# power_distribution_pcb.net
KiCad netlist of a schematic drawn in EAGLE
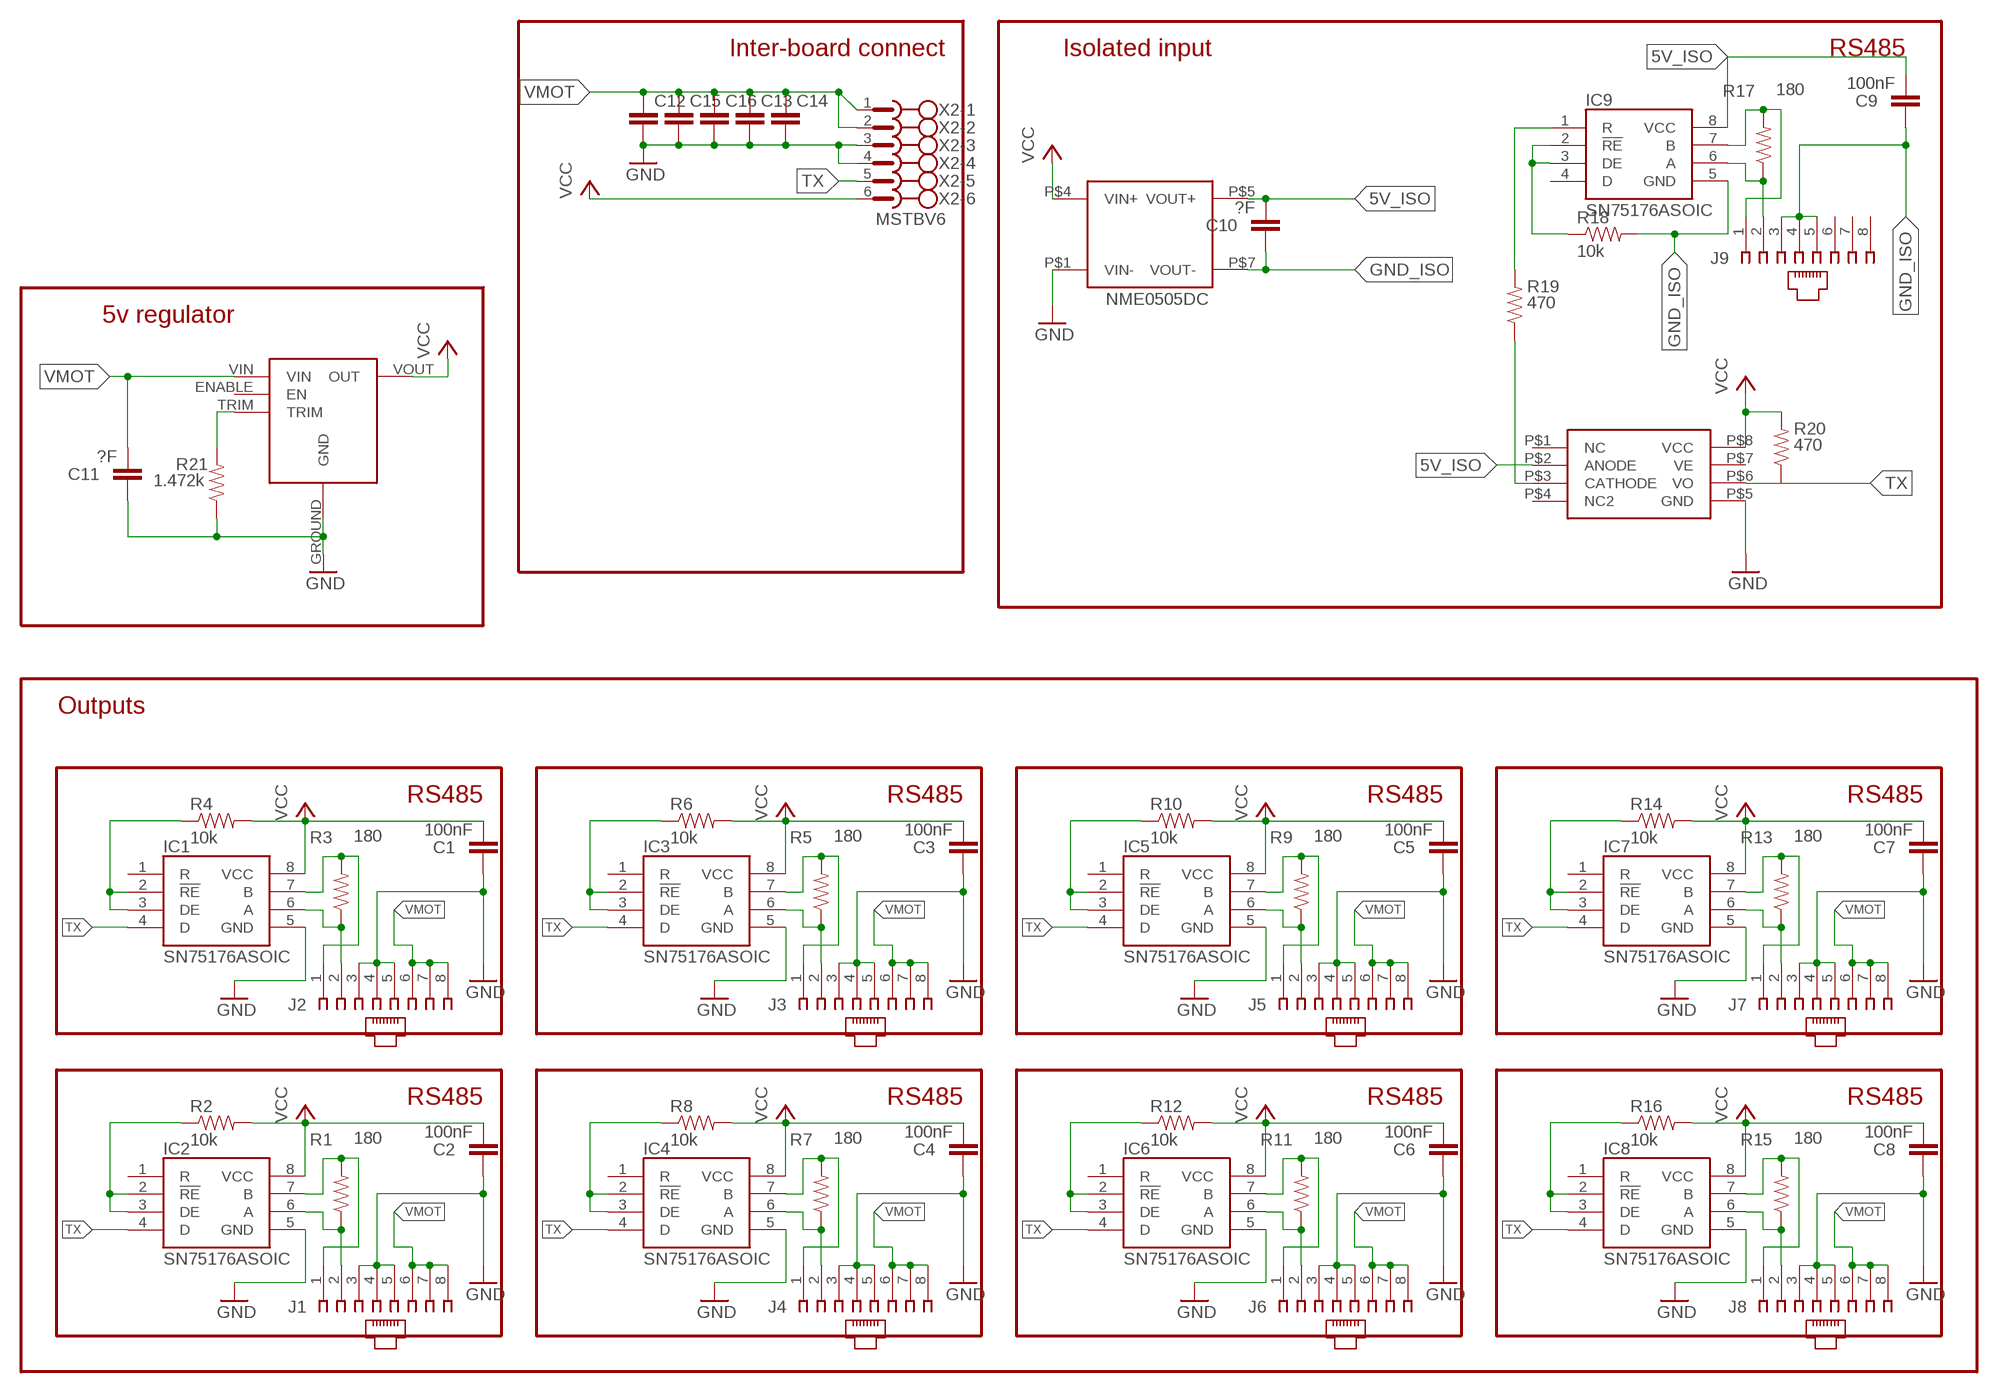
[diagram p0: schematic, sheet 1]

(export (version "E")
  (design (tool "Eeschema 10.0.6"))
  (components
    (comp (ref "C1")
      (value "100nF")
      (footprint "eagle-import:0805")
      (libsource (lib "eagle-import") (part "CAP0805"))
    )
    (comp (ref "C2")
      (value "100nF")
      (footprint "eagle-import:0805")
      (libsource (lib "eagle-import") (part "CAP0805"))
    )
    (comp (ref "C3")
      (value "100nF")
      (footprint "eagle-import:0805")
      (libsource (lib "eagle-import") (part "CAP0805"))
    )
    (comp (ref "C4")
      (value "100nF")
      (footprint "eagle-import:0805")
      (libsource (lib "eagle-import") (part "CAP0805"))
    )
    (comp (ref "C5")
      (value "100nF")
      (footprint "eagle-import:0805")
      (libsource (lib "eagle-import") (part "CAP0805"))
    )
    (comp (ref "C6")
      (value "100nF")
      (footprint "eagle-import:0805")
      (libsource (lib "eagle-import") (part "CAP0805"))
    )
    (comp (ref "C7")
      (value "100nF")
      (footprint "eagle-import:0805")
      (libsource (lib "eagle-import") (part "CAP0805"))
    )
    (comp (ref "C8")
      (value "100nF")
      (footprint "eagle-import:0805")
      (libsource (lib "eagle-import") (part "CAP0805"))
    )
    (comp (ref "C9")
      (value "100nF")
      (footprint "eagle-import:0805")
      (libsource (lib "eagle-import") (part "CAP0805"))
    )
    (comp (ref "C10")
      (value "?F")
      (footprint "eagle-import:0805")
      (libsource (lib "eagle-import") (part "CAP0805"))
    )
    (comp (ref "C11")
      (value "?F")
      (footprint "eagle-import:0805")
      (libsource (lib "eagle-import") (part "CAP0805"))
    )
    (comp (ref "C12")
      (value "CAP1210")
      (footprint "eagle-import:1210")
      (libsource (lib "eagle-import") (part "CAP1210"))
    )
    (comp (ref "C13")
      (value "CAP1210")
      (footprint "eagle-import:1210")
      (libsource (lib "eagle-import") (part "CAP1210"))
    )
    (comp (ref "C14")
      (value "CAP1210")
      (footprint "eagle-import:1210")
      (libsource (lib "eagle-import") (part "CAP1210"))
    )
    (comp (ref "C15")
      (value "CAP1210")
      (footprint "eagle-import:1210")
      (libsource (lib "eagle-import") (part "CAP1210"))
    )
    (comp (ref "C16")
      (value "CAP1210")
      (footprint "eagle-import:1210")
      (libsource (lib "eagle-import") (part "CAP1210"))
    )
    (comp (ref "IC1")
      (value "SN75176ASOIC")
      (footprint "eagle-import:SO08")
      (libsource (lib "eagle-import") (part "SN75176ASOIC"))
    )
    (comp (ref "IC2")
      (value "SN75176ASOIC")
      (footprint "eagle-import:SO08")
      (libsource (lib "eagle-import") (part "SN75176ASOIC"))
    )
    (comp (ref "IC3")
      (value "SN75176ASOIC")
      (footprint "eagle-import:SO08")
      (libsource (lib "eagle-import") (part "SN75176ASOIC"))
    )
    (comp (ref "IC4")
      (value "SN75176ASOIC")
      (footprint "eagle-import:SO08")
      (libsource (lib "eagle-import") (part "SN75176ASOIC"))
    )
    (comp (ref "IC5")
      (value "SN75176ASOIC")
      (footprint "eagle-import:SO08")
      (libsource (lib "eagle-import") (part "SN75176ASOIC"))
    )
    (comp (ref "IC6")
      (value "SN75176ASOIC")
      (footprint "eagle-import:SO08")
      (libsource (lib "eagle-import") (part "SN75176ASOIC"))
    )
    (comp (ref "IC7")
      (value "SN75176ASOIC")
      (footprint "eagle-import:SO08")
      (libsource (lib "eagle-import") (part "SN75176ASOIC"))
    )
    (comp (ref "IC8")
      (value "SN75176ASOIC")
      (footprint "eagle-import:SO08")
      (libsource (lib "eagle-import") (part "SN75176ASOIC"))
    )
    (comp (ref "IC9")
      (value "SN75176ASOIC")
      (footprint "eagle-import:SO08")
      (libsource (lib "eagle-import") (part "SN75176ASOIC"))
    )
    (comp (ref "J1")
      (value "520426-4")
      (footprint "eagle-import:520426-4")
      (libsource (lib "eagle-import") (part "520426-4"))
    )
    (comp (ref "J2")
      (value "520426-4")
      (footprint "eagle-import:520426-4")
      (libsource (lib "eagle-import") (part "520426-4"))
    )
    (comp (ref "J3")
      (value "520426-4")
      (footprint "eagle-import:520426-4")
      (libsource (lib "eagle-import") (part "520426-4"))
    )
    (comp (ref "J4")
      (value "520426-4")
      (footprint "eagle-import:520426-4")
      (libsource (lib "eagle-import") (part "520426-4"))
    )
    (comp (ref "J5")
      (value "520426-4")
      (footprint "eagle-import:520426-4")
      (libsource (lib "eagle-import") (part "520426-4"))
    )
    (comp (ref "J6")
      (value "520426-4")
      (footprint "eagle-import:520426-4")
      (libsource (lib "eagle-import") (part "520426-4"))
    )
    (comp (ref "J7")
      (value "520426-4")
      (footprint "eagle-import:520426-4")
      (libsource (lib "eagle-import") (part "520426-4"))
    )
    (comp (ref "J8")
      (value "520426-4")
      (footprint "eagle-import:520426-4")
      (libsource (lib "eagle-import") (part "520426-4"))
    )
    (comp (ref "J9")
      (value "520426-4")
      (footprint "eagle-import:520426-4")
      (libsource (lib "eagle-import") (part "520426-4"))
    )
    (comp (ref "R1")
      (value "180")
      (footprint "eagle-import:0805")
      (libsource (lib "eagle-import") (part "RESISTOR"))
    )
    (comp (ref "R2")
      (value "10k")
      (footprint "eagle-import:0805")
      (libsource (lib "eagle-import") (part "RESISTOR"))
    )
    (comp (ref "R3")
      (value "180")
      (footprint "eagle-import:0805")
      (libsource (lib "eagle-import") (part "RESISTOR"))
    )
    (comp (ref "R4")
      (value "10k")
      (footprint "eagle-import:0805")
      (libsource (lib "eagle-import") (part "RESISTOR"))
    )
    (comp (ref "R5")
      (value "180")
      (footprint "eagle-import:0805")
      (libsource (lib "eagle-import") (part "RESISTOR"))
    )
    (comp (ref "R6")
      (value "10k")
      (footprint "eagle-import:0805")
      (libsource (lib "eagle-import") (part "RESISTOR"))
    )
    (comp (ref "R7")
      (value "180")
      (footprint "eagle-import:0805")
      (libsource (lib "eagle-import") (part "RESISTOR"))
    )
    (comp (ref "R8")
      (value "10k")
      (footprint "eagle-import:0805")
      (libsource (lib "eagle-import") (part "RESISTOR"))
    )
    (comp (ref "R9")
      (value "180")
      (footprint "eagle-import:0805")
      (libsource (lib "eagle-import") (part "RESISTOR"))
    )
    (comp (ref "R10")
      (value "10k")
      (footprint "eagle-import:0805")
      (libsource (lib "eagle-import") (part "RESISTOR"))
    )
    (comp (ref "R11")
      (value "180")
      (footprint "eagle-import:0805")
      (libsource (lib "eagle-import") (part "RESISTOR"))
    )
    (comp (ref "R12")
      (value "10k")
      (footprint "eagle-import:0805")
      (libsource (lib "eagle-import") (part "RESISTOR"))
    )
    (comp (ref "R13")
      (value "180")
      (footprint "eagle-import:0805")
      (libsource (lib "eagle-import") (part "RESISTOR"))
    )
    (comp (ref "R14")
      (value "10k")
      (footprint "eagle-import:0805")
      (libsource (lib "eagle-import") (part "RESISTOR"))
    )
    (comp (ref "R15")
      (value "180")
      (footprint "eagle-import:0805")
      (libsource (lib "eagle-import") (part "RESISTOR"))
    )
    (comp (ref "R16")
      (value "10k")
      (footprint "eagle-import:0805")
      (libsource (lib "eagle-import") (part "RESISTOR"))
    )
    (comp (ref "R17")
      (value "180")
      (footprint "eagle-import:0805")
      (libsource (lib "eagle-import") (part "RESISTOR"))
    )
    (comp (ref "R18")
      (value "10k")
      (footprint "eagle-import:0805")
      (libsource (lib "eagle-import") (part "RESISTOR"))
    )
    (comp (ref "R19")
      (value "470")
      (footprint "eagle-import:0805")
      (libsource (lib "eagle-import") (part "RESISTOR"))
    )
    (comp (ref "R20")
      (value "470")
      (footprint "eagle-import:0805")
      (libsource (lib "eagle-import") (part "RESISTOR"))
    )
    (comp (ref "R21")
      (value "1.472k")
      (footprint "eagle-import:0805")
      (libsource (lib "eagle-import") (part "RESISTOR"))
    )
    (comp (ref "U$1")
      (value "NME0505DC")
      (footprint "eagle-import:NME0505DC")
      (libsource (lib "eagle-import") (part "NME0505DC"))
    )
    (comp (ref "U$2")
      (value "OKI-T/3-W40N-C")
      (footprint "eagle-import:OKI-T_3-W40N-C")
      (libsource (lib "eagle-import") (part "OKI-T/3-W40N-C"))
    )
    (comp (ref "U$3")
      (value "6N137")
      (footprint "eagle-import:8_SOIC")
      (libsource (lib "eagle-import") (part "6N137"))
    )
    (comp (ref "X2")
      (value "MSTBV6")
      (footprint "eagle-import:MSTBV6")
      (fields (field (name "MPN") "MSTBV 2,5/6-GF-5.08"))
      (libsource (lib "eagle-import") (part "MSTBV6"))
    )
  )
  (nets
    (net (code "1") (name "5V_ISO") (class "Default")
      (node (ref "C10") (pin "2") (pinfunction "2_2") (pintype "passive"))
      (node (ref "C9") (pin "2") (pinfunction "2_2") (pintype "passive"))
      (node (ref "IC9") (pin "8") (pinfunction "VCC_8") (pintype "bidirectional"))
      (node (ref "U$1") (pin "P$5") (pinfunction "VOUT+_P$5") (pintype "bidirectional"))
      (node (ref "U$3") (pin "P$2") (pinfunction "ANODE_P$2") (pintype "bidirectional"))
    )
    (net (code "2") (name "GND") (class "Default")
      (node (ref "C1") (pin "1") (pinfunction "1_1") (pintype "passive"))
      (node (ref "C11") (pin "1") (pinfunction "1_1") (pintype "passive"))
      (node (ref "C12") (pin "2") (pinfunction "2_2") (pintype "passive"))
      (node (ref "C13") (pin "2") (pinfunction "2_2") (pintype "passive"))
      (node (ref "C14") (pin "2") (pinfunction "2_2") (pintype "passive"))
      (node (ref "C15") (pin "2") (pinfunction "2_2") (pintype "passive"))
      (node (ref "C16") (pin "2") (pinfunction "2_2") (pintype "passive"))
      (node (ref "C2") (pin "1") (pinfunction "1_1") (pintype "passive"))
      (node (ref "C3") (pin "1") (pinfunction "1_1") (pintype "passive"))
      (node (ref "C4") (pin "1") (pinfunction "1_1") (pintype "passive"))
      (node (ref "C5") (pin "1") (pinfunction "1_1") (pintype "passive"))
      (node (ref "C6") (pin "1") (pinfunction "1_1") (pintype "passive"))
      (node (ref "C7") (pin "1") (pinfunction "1_1") (pintype "passive"))
      (node (ref "C8") (pin "1") (pinfunction "1_1") (pintype "passive"))
      (node (ref "IC1") (pin "5") (pinfunction "GND_5") (pintype "bidirectional"))
      (node (ref "IC2") (pin "5") (pinfunction "GND_5") (pintype "bidirectional"))
      (node (ref "IC3") (pin "5") (pinfunction "GND_5") (pintype "bidirectional"))
      (node (ref "IC4") (pin "5") (pinfunction "GND_5") (pintype "bidirectional"))
      (node (ref "IC5") (pin "5") (pinfunction "GND_5") (pintype "bidirectional"))
      (node (ref "IC6") (pin "5") (pinfunction "GND_5") (pintype "bidirectional"))
      (node (ref "IC7") (pin "5") (pinfunction "GND_5") (pintype "bidirectional"))
      (node (ref "IC8") (pin "5") (pinfunction "GND_5") (pintype "bidirectional"))
      (node (ref "J1") (pin "3") (pinfunction "3_3") (pintype "passive"))
      (node (ref "J1") (pin "4") (pinfunction "4_4") (pintype "passive"))
      (node (ref "J1") (pin "5") (pinfunction "5_5") (pintype "passive"))
      (node (ref "J2") (pin "3") (pinfunction "3_3") (pintype "passive"))
      (node (ref "J2") (pin "4") (pinfunction "4_4") (pintype "passive"))
      (node (ref "J2") (pin "5") (pinfunction "5_5") (pintype "passive"))
      (node (ref "J3") (pin "3") (pinfunction "3_3") (pintype "passive"))
      (node (ref "J3") (pin "4") (pinfunction "4_4") (pintype "passive"))
      (node (ref "J3") (pin "5") (pinfunction "5_5") (pintype "passive"))
      (node (ref "J4") (pin "3") (pinfunction "3_3") (pintype "passive"))
      (node (ref "J4") (pin "4") (pinfunction "4_4") (pintype "passive"))
      (node (ref "J4") (pin "5") (pinfunction "5_5") (pintype "passive"))
      (node (ref "J5") (pin "3") (pinfunction "3_3") (pintype "passive"))
      (node (ref "J5") (pin "4") (pinfunction "4_4") (pintype "passive"))
      (node (ref "J5") (pin "5") (pinfunction "5_5") (pintype "passive"))
      (node (ref "J6") (pin "3") (pinfunction "3_3") (pintype "passive"))
      (node (ref "J6") (pin "4") (pinfunction "4_4") (pintype "passive"))
      (node (ref "J6") (pin "5") (pinfunction "5_5") (pintype "passive"))
      (node (ref "J7") (pin "3") (pinfunction "3_3") (pintype "passive"))
      (node (ref "J7") (pin "4") (pinfunction "4_4") (pintype "passive"))
      (node (ref "J7") (pin "5") (pinfunction "5_5") (pintype "passive"))
      (node (ref "J8") (pin "3") (pinfunction "3_3") (pintype "passive"))
      (node (ref "J8") (pin "4") (pinfunction "4_4") (pintype "passive"))
      (node (ref "J8") (pin "5") (pinfunction "5_5") (pintype "passive"))
      (node (ref "R21") (pin "1") (pinfunction "1_1") (pintype "passive"))
      (node (ref "U$1") (pin "P$1") (pinfunction "VIN-_P$1") (pintype "bidirectional"))
      (node (ref "U$2") (pin "GROUND") (pinfunction "GND_GROUND") (pintype "bidirectional"))
      (node (ref "U$3") (pin "P$5") (pinfunction "GND_P$5") (pintype "bidirectional"))
      (node (ref "X2") (pin "3") (pinfunction "1_3") (pintype "passive"))
      (node (ref "X2") (pin "4") (pinfunction "1_4") (pintype "passive"))
    )
    (net (code "3") (name "GND_ISO") (class "Default")
      (node (ref "C10") (pin "1") (pinfunction "1_1") (pintype "passive"))
      (node (ref "C9") (pin "1") (pinfunction "1_1") (pintype "passive"))
      (node (ref "IC9") (pin "5") (pinfunction "GND_5") (pintype "bidirectional"))
      (node (ref "J9") (pin "3") (pinfunction "3_3") (pintype "passive"))
      (node (ref "J9") (pin "4") (pinfunction "4_4") (pintype "passive"))
      (node (ref "J9") (pin "5") (pinfunction "5_5") (pintype "passive"))
      (node (ref "R18") (pin "2") (pinfunction "2_2") (pintype "passive"))
      (node (ref "U$1") (pin "P$7") (pinfunction "VOUT-_P$7") (pintype "bidirectional"))
    )
    (net (code "4") (name "Net-(IC1-A)") (class "Default")
      (node (ref "IC1") (pin "6") (pinfunction "A_6") (pintype "bidirectional"))
      (node (ref "J2") (pin "2") (pinfunction "2_2") (pintype "passive"))
      (node (ref "R3") (pin "1") (pinfunction "1_1") (pintype "passive"))
    )
    (net (code "5") (name "Net-(IC1-B)") (class "Default")
      (node (ref "IC1") (pin "7") (pinfunction "B_7") (pintype "bidirectional"))
      (node (ref "J2") (pin "1") (pinfunction "1_1") (pintype "passive"))
      (node (ref "R3") (pin "2") (pinfunction "2_2") (pintype "passive"))
    )
    (net (code "6") (name "Net-(IC1-DE)") (class "Default")
      (node (ref "IC1") (pin "2") (pinfunction "~{RE}_2") (pintype "bidirectional"))
      (node (ref "IC1") (pin "3") (pinfunction "DE_3") (pintype "bidirectional"))
      (node (ref "R4") (pin "1") (pinfunction "1_1") (pintype "passive"))
    )
    (net (code "7") (name "Net-(IC2-A)") (class "Default")
      (node (ref "IC2") (pin "6") (pinfunction "A_6") (pintype "bidirectional"))
      (node (ref "J1") (pin "2") (pinfunction "2_2") (pintype "passive"))
      (node (ref "R1") (pin "1") (pinfunction "1_1") (pintype "passive"))
    )
    (net (code "8") (name "Net-(IC2-B)") (class "Default")
      (node (ref "IC2") (pin "7") (pinfunction "B_7") (pintype "bidirectional"))
      (node (ref "J1") (pin "1") (pinfunction "1_1") (pintype "passive"))
      (node (ref "R1") (pin "2") (pinfunction "2_2") (pintype "passive"))
    )
    (net (code "9") (name "Net-(IC2-DE)") (class "Default")
      (node (ref "IC2") (pin "2") (pinfunction "~{RE}_2") (pintype "bidirectional"))
      (node (ref "IC2") (pin "3") (pinfunction "DE_3") (pintype "bidirectional"))
      (node (ref "R2") (pin "1") (pinfunction "1_1") (pintype "passive"))
    )
    (net (code "10") (name "Net-(IC3-A)") (class "Default")
      (node (ref "IC3") (pin "6") (pinfunction "A_6") (pintype "bidirectional"))
      (node (ref "J3") (pin "2") (pinfunction "2_2") (pintype "passive"))
      (node (ref "R5") (pin "1") (pinfunction "1_1") (pintype "passive"))
    )
    (net (code "11") (name "Net-(IC3-B)") (class "Default")
      (node (ref "IC3") (pin "7") (pinfunction "B_7") (pintype "bidirectional"))
      (node (ref "J3") (pin "1") (pinfunction "1_1") (pintype "passive"))
      (node (ref "R5") (pin "2") (pinfunction "2_2") (pintype "passive"))
    )
    (net (code "12") (name "Net-(IC3-DE)") (class "Default")
      (node (ref "IC3") (pin "2") (pinfunction "~{RE}_2") (pintype "bidirectional"))
      (node (ref "IC3") (pin "3") (pinfunction "DE_3") (pintype "bidirectional"))
      (node (ref "R6") (pin "1") (pinfunction "1_1") (pintype "passive"))
    )
    (net (code "13") (name "Net-(IC4-A)") (class "Default")
      (node (ref "IC4") (pin "6") (pinfunction "A_6") (pintype "bidirectional"))
      (node (ref "J4") (pin "2") (pinfunction "2_2") (pintype "passive"))
      (node (ref "R7") (pin "1") (pinfunction "1_1") (pintype "passive"))
    )
    (net (code "14") (name "Net-(IC4-B)") (class "Default")
      (node (ref "IC4") (pin "7") (pinfunction "B_7") (pintype "bidirectional"))
      (node (ref "J4") (pin "1") (pinfunction "1_1") (pintype "passive"))
      (node (ref "R7") (pin "2") (pinfunction "2_2") (pintype "passive"))
    )
    (net (code "15") (name "Net-(IC4-DE)") (class "Default")
      (node (ref "IC4") (pin "2") (pinfunction "~{RE}_2") (pintype "bidirectional"))
      (node (ref "IC4") (pin "3") (pinfunction "DE_3") (pintype "bidirectional"))
      (node (ref "R8") (pin "1") (pinfunction "1_1") (pintype "passive"))
    )
    (net (code "16") (name "Net-(IC5-A)") (class "Default")
      (node (ref "IC5") (pin "6") (pinfunction "A_6") (pintype "bidirectional"))
      (node (ref "J5") (pin "2") (pinfunction "2_2") (pintype "passive"))
      (node (ref "R9") (pin "1") (pinfunction "1_1") (pintype "passive"))
    )
    (net (code "17") (name "Net-(IC5-B)") (class "Default")
      (node (ref "IC5") (pin "7") (pinfunction "B_7") (pintype "bidirectional"))
      (node (ref "J5") (pin "1") (pinfunction "1_1") (pintype "passive"))
      (node (ref "R9") (pin "2") (pinfunction "2_2") (pintype "passive"))
    )
    (net (code "18") (name "Net-(IC5-DE)") (class "Default")
      (node (ref "IC5") (pin "2") (pinfunction "~{RE}_2") (pintype "bidirectional"))
      (node (ref "IC5") (pin "3") (pinfunction "DE_3") (pintype "bidirectional"))
      (node (ref "R10") (pin "1") (pinfunction "1_1") (pintype "passive"))
    )
    (net (code "19") (name "Net-(IC6-A)") (class "Default")
      (node (ref "IC6") (pin "6") (pinfunction "A_6") (pintype "bidirectional"))
      (node (ref "J6") (pin "2") (pinfunction "2_2") (pintype "passive"))
      (node (ref "R11") (pin "1") (pinfunction "1_1") (pintype "passive"))
    )
    (net (code "20") (name "Net-(IC6-B)") (class "Default")
      (node (ref "IC6") (pin "7") (pinfunction "B_7") (pintype "bidirectional"))
      (node (ref "J6") (pin "1") (pinfunction "1_1") (pintype "passive"))
      (node (ref "R11") (pin "2") (pinfunction "2_2") (pintype "passive"))
    )
    (net (code "21") (name "Net-(IC6-DE)") (class "Default")
      (node (ref "IC6") (pin "2") (pinfunction "~{RE}_2") (pintype "bidirectional"))
      (node (ref "IC6") (pin "3") (pinfunction "DE_3") (pintype "bidirectional"))
      (node (ref "R12") (pin "1") (pinfunction "1_1") (pintype "passive"))
    )
    (net (code "22") (name "Net-(IC7-A)") (class "Default")
      (node (ref "IC7") (pin "6") (pinfunction "A_6") (pintype "bidirectional"))
      (node (ref "J7") (pin "2") (pinfunction "2_2") (pintype "passive"))
      (node (ref "R13") (pin "1") (pinfunction "1_1") (pintype "passive"))
    )
    (net (code "23") (name "Net-(IC7-B)") (class "Default")
      (node (ref "IC7") (pin "7") (pinfunction "B_7") (pintype "bidirectional"))
      (node (ref "J7") (pin "1") (pinfunction "1_1") (pintype "passive"))
      (node (ref "R13") (pin "2") (pinfunction "2_2") (pintype "passive"))
    )
    (net (code "24") (name "Net-(IC7-DE)") (class "Default")
      (node (ref "IC7") (pin "2") (pinfunction "~{RE}_2") (pintype "bidirectional"))
      (node (ref "IC7") (pin "3") (pinfunction "DE_3") (pintype "bidirectional"))
      (node (ref "R14") (pin "1") (pinfunction "1_1") (pintype "passive"))
    )
    (net (code "25") (name "Net-(IC8-A)") (class "Default")
      (node (ref "IC8") (pin "6") (pinfunction "A_6") (pintype "bidirectional"))
      (node (ref "J8") (pin "2") (pinfunction "2_2") (pintype "passive"))
      (node (ref "R15") (pin "1") (pinfunction "1_1") (pintype "passive"))
    )
    (net (code "26") (name "Net-(IC8-B)") (class "Default")
      (node (ref "IC8") (pin "7") (pinfunction "B_7") (pintype "bidirectional"))
      (node (ref "J8") (pin "1") (pinfunction "1_1") (pintype "passive"))
      (node (ref "R15") (pin "2") (pinfunction "2_2") (pintype "passive"))
    )
    (net (code "27") (name "Net-(IC8-DE)") (class "Default")
      (node (ref "IC8") (pin "2") (pinfunction "~{RE}_2") (pintype "bidirectional"))
      (node (ref "IC8") (pin "3") (pinfunction "DE_3") (pintype "bidirectional"))
      (node (ref "R16") (pin "1") (pinfunction "1_1") (pintype "passive"))
    )
    (net (code "28") (name "Net-(IC9-A)") (class "Default")
      (node (ref "IC9") (pin "6") (pinfunction "A_6") (pintype "bidirectional"))
      (node (ref "J9") (pin "2") (pinfunction "2_2") (pintype "passive"))
      (node (ref "R17") (pin "1") (pinfunction "1_1") (pintype "passive"))
    )
    (net (code "29") (name "Net-(IC9-B)") (class "Default")
      (node (ref "IC9") (pin "7") (pinfunction "B_7") (pintype "bidirectional"))
      (node (ref "J9") (pin "1") (pinfunction "1_1") (pintype "passive"))
      (node (ref "R17") (pin "2") (pinfunction "2_2") (pintype "passive"))
    )
    (net (code "30") (name "Net-(IC9-DE)") (class "Default")
      (node (ref "IC9") (pin "2") (pinfunction "~{RE}_2") (pintype "bidirectional"))
      (node (ref "IC9") (pin "3") (pinfunction "DE_3") (pintype "bidirectional"))
      (node (ref "R18") (pin "1") (pinfunction "1_1") (pintype "passive"))
    )
    (net (code "31") (name "Net-(IC9-R)") (class "Default")
      (node (ref "IC9") (pin "1") (pinfunction "R_1") (pintype "bidirectional"))
      (node (ref "R19") (pin "2") (pinfunction "2_2") (pintype "passive"))
    )
    (net (code "32") (name "Net-(R21-Pad2)") (class "Default")
      (node (ref "R21") (pin "2") (pinfunction "2_2") (pintype "passive"))
      (node (ref "U$2") (pin "TRIM") (pinfunction "TRIM_TRIM") (pintype "bidirectional"))
    )
    (net (code "33") (name "Net-(U$3-CATHODE)") (class "Default")
      (node (ref "R19") (pin "1") (pinfunction "1_1") (pintype "passive"))
      (node (ref "U$3") (pin "P$3") (pinfunction "CATHODE_P$3") (pintype "bidirectional"))
    )
    (net (code "34") (name "TX") (class "Default")
      (node (ref "IC1") (pin "4") (pinfunction "D_4") (pintype "bidirectional"))
      (node (ref "IC2") (pin "4") (pinfunction "D_4") (pintype "bidirectional"))
      (node (ref "IC3") (pin "4") (pinfunction "D_4") (pintype "bidirectional"))
      (node (ref "IC4") (pin "4") (pinfunction "D_4") (pintype "bidirectional"))
      (node (ref "IC5") (pin "4") (pinfunction "D_4") (pintype "bidirectional"))
      (node (ref "IC6") (pin "4") (pinfunction "D_4") (pintype "bidirectional"))
      (node (ref "IC7") (pin "4") (pinfunction "D_4") (pintype "bidirectional"))
      (node (ref "IC8") (pin "4") (pinfunction "D_4") (pintype "bidirectional"))
      (node (ref "R20") (pin "1") (pinfunction "1_1") (pintype "passive"))
      (node (ref "U$3") (pin "P$6") (pinfunction "VO_P$6") (pintype "bidirectional"))
      (node (ref "X2") (pin "5") (pinfunction "1_5") (pintype "passive"))
    )
    (net (code "35") (name "VCC") (class "Default")
      (node (ref "C1") (pin "2") (pinfunction "2_2") (pintype "passive"))
      (node (ref "C2") (pin "2") (pinfunction "2_2") (pintype "passive"))
      (node (ref "C3") (pin "2") (pinfunction "2_2") (pintype "passive"))
      (node (ref "C4") (pin "2") (pinfunction "2_2") (pintype "passive"))
      (node (ref "C5") (pin "2") (pinfunction "2_2") (pintype "passive"))
      (node (ref "C6") (pin "2") (pinfunction "2_2") (pintype "passive"))
      (node (ref "C7") (pin "2") (pinfunction "2_2") (pintype "passive"))
      (node (ref "C8") (pin "2") (pinfunction "2_2") (pintype "passive"))
      (node (ref "IC1") (pin "8") (pinfunction "VCC_8") (pintype "bidirectional"))
      (node (ref "IC2") (pin "8") (pinfunction "VCC_8") (pintype "bidirectional"))
      (node (ref "IC3") (pin "8") (pinfunction "VCC_8") (pintype "bidirectional"))
      (node (ref "IC4") (pin "8") (pinfunction "VCC_8") (pintype "bidirectional"))
      (node (ref "IC5") (pin "8") (pinfunction "VCC_8") (pintype "bidirectional"))
      (node (ref "IC6") (pin "8") (pinfunction "VCC_8") (pintype "bidirectional"))
      (node (ref "IC7") (pin "8") (pinfunction "VCC_8") (pintype "bidirectional"))
      (node (ref "IC8") (pin "8") (pinfunction "VCC_8") (pintype "bidirectional"))
      (node (ref "R10") (pin "2") (pinfunction "2_2") (pintype "passive"))
      (node (ref "R12") (pin "2") (pinfunction "2_2") (pintype "passive"))
      (node (ref "R14") (pin "2") (pinfunction "2_2") (pintype "passive"))
      (node (ref "R16") (pin "2") (pinfunction "2_2") (pintype "passive"))
      (node (ref "R2") (pin "2") (pinfunction "2_2") (pintype "passive"))
      (node (ref "R20") (pin "2") (pinfunction "2_2") (pintype "passive"))
      (node (ref "R4") (pin "2") (pinfunction "2_2") (pintype "passive"))
      (node (ref "R6") (pin "2") (pinfunction "2_2") (pintype "passive"))
      (node (ref "R8") (pin "2") (pinfunction "2_2") (pintype "passive"))
      (node (ref "U$1") (pin "P$4") (pinfunction "VIN+_P$4") (pintype "bidirectional"))
      (node (ref "U$2") (pin "VOUT") (pinfunction "OUT_VOUT") (pintype "bidirectional"))
      (node (ref "U$3") (pin "P$8") (pinfunction "VCC_P$8") (pintype "bidirectional"))
      (node (ref "X2") (pin "6") (pinfunction "1_6") (pintype "passive"))
    )
    (net (code "36") (name "VMOT") (class "Default")
      (node (ref "C11") (pin "2") (pinfunction "2_2") (pintype "passive"))
      (node (ref "C12") (pin "1") (pinfunction "1_1") (pintype "passive"))
      (node (ref "C13") (pin "1") (pinfunction "1_1") (pintype "passive"))
      (node (ref "C14") (pin "1") (pinfunction "1_1") (pintype "passive"))
      (node (ref "C15") (pin "1") (pinfunction "1_1") (pintype "passive"))
      (node (ref "C16") (pin "1") (pinfunction "1_1") (pintype "passive"))
      (node (ref "J1") (pin "6") (pinfunction "6_6") (pintype "passive"))
      (node (ref "J1") (pin "7") (pinfunction "7_7") (pintype "passive"))
      (node (ref "J1") (pin "8") (pinfunction "8_8") (pintype "passive"))
      (node (ref "J2") (pin "6") (pinfunction "6_6") (pintype "passive"))
      (node (ref "J2") (pin "7") (pinfunction "7_7") (pintype "passive"))
      (node (ref "J2") (pin "8") (pinfunction "8_8") (pintype "passive"))
      (node (ref "J3") (pin "6") (pinfunction "6_6") (pintype "passive"))
      (node (ref "J3") (pin "7") (pinfunction "7_7") (pintype "passive"))
      (node (ref "J3") (pin "8") (pinfunction "8_8") (pintype "passive"))
      (node (ref "J4") (pin "6") (pinfunction "6_6") (pintype "passive"))
      (node (ref "J4") (pin "7") (pinfunction "7_7") (pintype "passive"))
      (node (ref "J4") (pin "8") (pinfunction "8_8") (pintype "passive"))
      (node (ref "J5") (pin "6") (pinfunction "6_6") (pintype "passive"))
      (node (ref "J5") (pin "7") (pinfunction "7_7") (pintype "passive"))
      (node (ref "J5") (pin "8") (pinfunction "8_8") (pintype "passive"))
      (node (ref "J6") (pin "6") (pinfunction "6_6") (pintype "passive"))
      (node (ref "J6") (pin "7") (pinfunction "7_7") (pintype "passive"))
      (node (ref "J6") (pin "8") (pinfunction "8_8") (pintype "passive"))
      (node (ref "J7") (pin "6") (pinfunction "6_6") (pintype "passive"))
      (node (ref "J7") (pin "7") (pinfunction "7_7") (pintype "passive"))
      (node (ref "J7") (pin "8") (pinfunction "8_8") (pintype "passive"))
      (node (ref "J8") (pin "6") (pinfunction "6_6") (pintype "passive"))
      (node (ref "J8") (pin "7") (pinfunction "7_7") (pintype "passive"))
      (node (ref "J8") (pin "8") (pinfunction "8_8") (pintype "passive"))
      (node (ref "U$2") (pin "VIN") (pinfunction "VIN_VIN") (pintype "bidirectional"))
      (node (ref "X2") (pin "1") (pinfunction "1_1") (pintype "passive"))
      (node (ref "X2") (pin "2") (pinfunction "1_2") (pintype "passive"))
    )
    (net (code "37") (name "unconnected-(IC1-R-Pad1)") (class "Default")
      (node (ref "IC1") (pin "1") (pinfunction "R_1") (pintype "bidirectional"))
    )
    (net (code "38") (name "unconnected-(IC2-R-Pad1)") (class "Default")
      (node (ref "IC2") (pin "1") (pinfunction "R_1") (pintype "bidirectional"))
    )
    (net (code "39") (name "unconnected-(IC3-R-Pad1)") (class "Default")
      (node (ref "IC3") (pin "1") (pinfunction "R_1") (pintype "bidirectional"))
    )
    (net (code "40") (name "unconnected-(IC4-R-Pad1)") (class "Default")
      (node (ref "IC4") (pin "1") (pinfunction "R_1") (pintype "bidirectional"))
    )
    (net (code "41") (name "unconnected-(IC5-R-Pad1)") (class "Default")
      (node (ref "IC5") (pin "1") (pinfunction "R_1") (pintype "bidirectional"))
    )
    (net (code "42") (name "unconnected-(IC6-R-Pad1)") (class "Default")
      (node (ref "IC6") (pin "1") (pinfunction "R_1") (pintype "bidirectional"))
    )
    (net (code "43") (name "unconnected-(IC7-R-Pad1)") (class "Default")
      (node (ref "IC7") (pin "1") (pinfunction "R_1") (pintype "bidirectional"))
    )
    (net (code "44") (name "unconnected-(IC8-R-Pad1)") (class "Default")
      (node (ref "IC8") (pin "1") (pinfunction "R_1") (pintype "bidirectional"))
    )
    (net (code "45") (name "unconnected-(IC9-D-Pad4)") (class "Default")
      (node (ref "IC9") (pin "4") (pinfunction "D_4") (pintype "bidirectional"))
    )
    (net (code "46") (name "unconnected-(J9-Pad6)") (class "Default")
      (node (ref "J9") (pin "6") (pinfunction "6_6") (pintype "passive"))
    )
    (net (code "47") (name "unconnected-(J9-Pad7)") (class "Default")
      (node (ref "J9") (pin "7") (pinfunction "7_7") (pintype "passive"))
    )
    (net (code "48") (name "unconnected-(J9-Pad8)") (class "Default")
      (node (ref "J9") (pin "8") (pinfunction "8_8") (pintype "passive"))
    )
    (net (code "49") (name "unconnected-(U$2-EN-PadENABLE)") (class "Default")
      (node (ref "U$2") (pin "ENABLE") (pinfunction "EN_ENABLE") (pintype "bidirectional"))
    )
    (net (code "50") (name "unconnected-(U$3-NC-PadP$1)") (class "Default")
      (node (ref "U$3") (pin "P$1") (pinfunction "NC_P$1") (pintype "bidirectional"))
    )
    (net (code "51") (name "unconnected-(U$3-NC2-PadP$4)") (class "Default")
      (node (ref "U$3") (pin "P$4") (pinfunction "NC2_P$4") (pintype "bidirectional"))
    )
    (net (code "52") (name "unconnected-(U$3-VE-PadP$7)") (class "Default")
      (node (ref "U$3") (pin "P$7") (pinfunction "VE_P$7") (pintype "bidirectional"))
    )
  )
)
